# Dout24x.net
KiCad netlist of a schematic drawn in Altium Designer
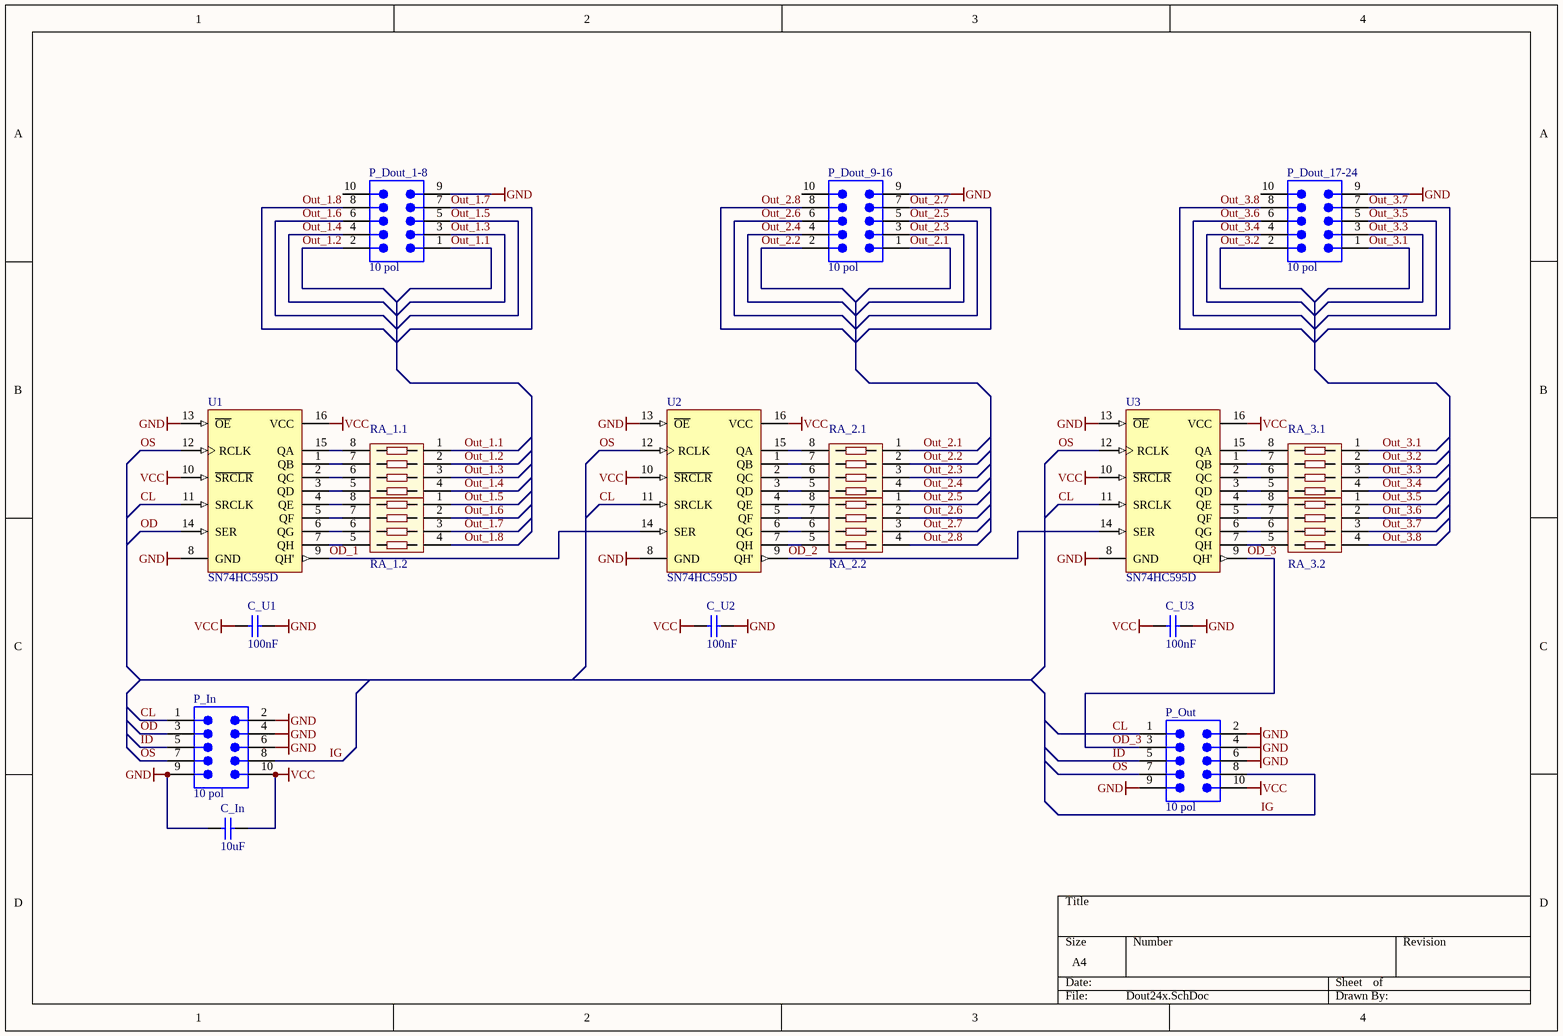
[diagram p0: Dout24x.SchDoc]

(export (version "E")
  (design (tool "Eeschema 10.0.6"))
  (components
    (comp (ref "C_In")
      (value "10uF")
      (footprint "1608[0603]")
      (description "Capacitor (Semiconductor SIM Model)")
      (fields (field (name "Comment") "Cap Semi") (field (name "PUBLISHER") "Altium Limited"))
      (libsource (lib "Miscellaneous Devices") (part "Cap Semi"))
    )
    (comp (ref "C_U1")
      (value "100nF")
      (footprint "1608[0603]")
      (description "Capacitor (Semiconductor SIM Model)")
      (fields (field (name "Comment") "Cap Semi") (field (name "PUBLISHER") "Altium Limited"))
      (libsource (lib "Miscellaneous Devices") (part "Cap Semi"))
    )
    (comp (ref "C_U2")
      (value "100nF")
      (footprint "1608[0603]")
      (description "Capacitor (Semiconductor SIM Model)")
      (fields (field (name "Comment") "Cap Semi") (field (name "PUBLISHER") "Altium Limited"))
      (libsource (lib "Miscellaneous Devices") (part "Cap Semi"))
    )
    (comp (ref "C_U3")
      (value "100nF")
      (footprint "1608[0603]")
      (description "Capacitor (Semiconductor SIM Model)")
      (fields (field (name "Comment") "Cap Semi") (field (name "PUBLISHER") "Altium Limited"))
      (libsource (lib "Miscellaneous Devices") (part "Cap Semi"))
    )
    (comp (ref "P_Dout_1-8")
      (value "10 pol")
      (footprint "918510x324")
      (fields (field (name "PUBLISHER") "Altium Limited"))
      (libsource (lib "HARTING IDC 2.54mm Pitch") (part "09 18 510 6324"))
    )
    (comp (ref "P_Dout_9-16")
      (value "10 pol")
      (footprint "918510x324")
      (fields (field (name "PUBLISHER") "Altium Limited"))
      (libsource (lib "HARTING IDC 2.54mm Pitch") (part "09 18 510 6324"))
    )
    (comp (ref "P_Dout_17-24")
      (value "10 pol")
      (footprint "918510x324")
      (fields (field (name "PUBLISHER") "Altium Limited"))
      (libsource (lib "HARTING IDC 2.54mm Pitch") (part "09 18 510 6324"))
    )
    (comp (ref "P_In")
      (value "10 pol")
      (footprint "918510x324")
      (fields (field (name "PUBLISHER") "Altium Limited"))
      (libsource (lib "") (part "09 18 510 6324_1"))
    )
    (comp (ref "P_Out")
      (value "10 pol")
      (footprint "918510x324")
      (fields (field (name "PUBLISHER") "Altium Limited"))
      (libsource (lib "") (part "09 18 510 6324_1"))
    )
    (comp (ref "RA_1.1")
      (value "EXB38")
      (footprint "Panasonic EXB38V:EXB38")
      (fields (field (name "PUBLISHER") "Altium Limited"))
      (libsource (lib "Panasonic Resistor Array") (part "4 Resistors Parallel"))
    )
    (comp (ref "RA_1.2")
      (value "EXB38")
      (footprint "Panasonic EXB38V:EXB38")
      (fields (field (name "PUBLISHER") "Altium Limited"))
      (libsource (lib "Panasonic Resistor Array") (part "4 Resistors Parallel"))
    )
    (comp (ref "RA_2.1")
      (value "EXB38")
      (footprint "Panasonic EXB38V:EXB38")
      (fields (field (name "PUBLISHER") "Altium Limited"))
      (libsource (lib "Panasonic Resistor Array") (part "4 Resistors Parallel"))
    )
    (comp (ref "RA_2.2")
      (value "EXB38")
      (footprint "Panasonic EXB38V:EXB38")
      (fields (field (name "PUBLISHER") "Altium Limited"))
      (libsource (lib "Panasonic Resistor Array") (part "4 Resistors Parallel"))
    )
    (comp (ref "RA_3.1")
      (value "EXB38")
      (footprint "Panasonic EXB38V:EXB38")
      (fields (field (name "PUBLISHER") "Altium Limited"))
      (libsource (lib "Panasonic Resistor Array") (part "4 Resistors Parallel"))
    )
    (comp (ref "RA_3.2")
      (value "EXB38")
      (footprint "Panasonic EXB38V:EXB38")
      (fields (field (name "PUBLISHER") "Altium Limited"))
      (libsource (lib "Panasonic Resistor Array") (part "4 Resistors Parallel"))
    )
    (comp (ref "U1")
      (value "SN74HC595D")
      (footprint "D016_N")
      (description "8-Bit Shift Register with 3-State Output Registers")
      (fields (field (name "PUBLISHER") "Altium Limited"))
      (libsource (lib "TI Logic Register") (part "SN74HC595D"))
    )
    (comp (ref "U2")
      (value "SN74HC595D")
      (footprint "D016_N")
      (description "8-Bit Shift Register with 3-State Output Registers")
      (fields (field (name "PUBLISHER") "Altium Limited"))
      (libsource (lib "TI Logic Register") (part "SN74HC595D"))
    )
    (comp (ref "U3")
      (value "SN74HC595D")
      (footprint "D016_N")
      (description "8-Bit Shift Register with 3-State Output Registers")
      (fields (field (name "PUBLISHER") "Altium Limited"))
      (libsource (lib "TI Logic Register") (part "SN74HC595D"))
    )
  )
  (nets
    (net (code "1") (name "/CL") (class "Default")
      (node (ref "P_In") (pin "1") (pinfunction "1_1") (pintype "passive"))
      (node (ref "P_Out") (pin "1") (pinfunction "1_1") (pintype "passive"))
      (node (ref "U1") (pin "11") (pinfunction "SRCLK_11") (pintype "input"))
      (node (ref "U2") (pin "11") (pinfunction "SRCLK_11") (pintype "input"))
      (node (ref "U3") (pin "11") (pinfunction "SRCLK_11") (pintype "input"))
    )
    (net (code "2") (name "/ID") (class "Default")
      (node (ref "P_In") (pin "5") (pinfunction "5_5") (pintype "passive"))
      (node (ref "P_Out") (pin "5") (pinfunction "5_5") (pintype "passive"))
    )
    (net (code "3") (name "/IG") (class "Default")
      (node (ref "P_In") (pin "8") (pinfunction "8_8") (pintype "passive"))
      (node (ref "P_Out") (pin "8") (pinfunction "8_8") (pintype "passive"))
    )
    (net (code "4") (name "/OD") (class "Default")
      (node (ref "P_In") (pin "3") (pinfunction "3_3") (pintype "passive"))
      (node (ref "U1") (pin "14") (pinfunction "SER_14") (pintype "input"))
    )
    (net (code "5") (name "/OD_1") (class "Default")
      (node (ref "U1") (pin "9") (pinfunction "QH'_9") (pintype "output"))
      (node (ref "U2") (pin "14") (pinfunction "SER_14") (pintype "input"))
    )
    (net (code "6") (name "/OD_2") (class "Default")
      (node (ref "U2") (pin "9") (pinfunction "QH'_9") (pintype "output"))
      (node (ref "U3") (pin "14") (pinfunction "SER_14") (pintype "input"))
    )
    (net (code "7") (name "/OD_3") (class "Default")
      (node (ref "P_Out") (pin "3") (pinfunction "3_3") (pintype "passive"))
      (node (ref "U3") (pin "9") (pinfunction "QH'_9") (pintype "output"))
    )
    (net (code "8") (name "/OS") (class "Default")
      (node (ref "P_In") (pin "7") (pinfunction "7_7") (pintype "passive"))
      (node (ref "P_Out") (pin "7") (pinfunction "7_7") (pintype "passive"))
      (node (ref "U1") (pin "12") (pinfunction "RCLK_12") (pintype "input"))
      (node (ref "U2") (pin "12") (pinfunction "RCLK_12") (pintype "input"))
      (node (ref "U3") (pin "12") (pinfunction "RCLK_12") (pintype "input"))
    )
    (net (code "9") (name "/Out_1.1") (class "Default")
      (node (ref "P_Dout_1-8") (pin "1") (pinfunction "1_1") (pintype "passive"))
      (node (ref "RA_1.1") (pin "1") (pinfunction "1_1") (pintype "passive"))
    )
    (net (code "10") (name "/Out_1.2") (class "Default")
      (node (ref "P_Dout_1-8") (pin "2") (pinfunction "2_2") (pintype "passive"))
      (node (ref "RA_1.1") (pin "2") (pinfunction "2_2") (pintype "passive"))
    )
    (net (code "11") (name "/Out_1.3") (class "Default")
      (node (ref "P_Dout_1-8") (pin "3") (pinfunction "3_3") (pintype "passive"))
      (node (ref "RA_1.1") (pin "3") (pinfunction "3_3") (pintype "passive"))
    )
    (net (code "12") (name "/Out_1.4") (class "Default")
      (node (ref "P_Dout_1-8") (pin "4") (pinfunction "4_4") (pintype "passive"))
      (node (ref "RA_1.1") (pin "4") (pinfunction "4_4") (pintype "passive"))
    )
    (net (code "13") (name "/Out_1.5") (class "Default")
      (node (ref "P_Dout_1-8") (pin "5") (pinfunction "5_5") (pintype "passive"))
      (node (ref "RA_1.2") (pin "1") (pinfunction "1_1") (pintype "passive"))
    )
    (net (code "14") (name "/Out_1.6") (class "Default")
      (node (ref "P_Dout_1-8") (pin "6") (pinfunction "6_6") (pintype "passive"))
      (node (ref "RA_1.2") (pin "2") (pinfunction "2_2") (pintype "passive"))
    )
    (net (code "15") (name "/Out_1.7") (class "Default")
      (node (ref "P_Dout_1-8") (pin "7") (pinfunction "7_7") (pintype "passive"))
      (node (ref "RA_1.2") (pin "3") (pinfunction "3_3") (pintype "passive"))
    )
    (net (code "16") (name "/Out_1.8") (class "Default")
      (node (ref "P_Dout_1-8") (pin "8") (pinfunction "8_8") (pintype "passive"))
      (node (ref "RA_1.2") (pin "4") (pinfunction "4_4") (pintype "passive"))
    )
    (net (code "17") (name "/Out_2.1") (class "Default")
      (node (ref "P_Dout_9-16") (pin "1") (pinfunction "1_1") (pintype "passive"))
      (node (ref "RA_2.1") (pin "1") (pinfunction "1_1") (pintype "passive"))
    )
    (net (code "18") (name "/Out_2.2") (class "Default")
      (node (ref "P_Dout_9-16") (pin "2") (pinfunction "2_2") (pintype "passive"))
      (node (ref "RA_2.1") (pin "2") (pinfunction "2_2") (pintype "passive"))
    )
    (net (code "19") (name "/Out_2.3") (class "Default")
      (node (ref "P_Dout_9-16") (pin "3") (pinfunction "3_3") (pintype "passive"))
      (node (ref "RA_2.1") (pin "3") (pinfunction "3_3") (pintype "passive"))
    )
    (net (code "20") (name "/Out_2.4") (class "Default")
      (node (ref "P_Dout_9-16") (pin "4") (pinfunction "4_4") (pintype "passive"))
      (node (ref "RA_2.1") (pin "4") (pinfunction "4_4") (pintype "passive"))
    )
    (net (code "21") (name "/Out_2.5") (class "Default")
      (node (ref "P_Dout_9-16") (pin "5") (pinfunction "5_5") (pintype "passive"))
      (node (ref "RA_2.2") (pin "1") (pinfunction "1_1") (pintype "passive"))
    )
    (net (code "22") (name "/Out_2.6") (class "Default")
      (node (ref "P_Dout_9-16") (pin "6") (pinfunction "6_6") (pintype "passive"))
      (node (ref "RA_2.2") (pin "2") (pinfunction "2_2") (pintype "passive"))
    )
    (net (code "23") (name "/Out_2.7") (class "Default")
      (node (ref "P_Dout_9-16") (pin "7") (pinfunction "7_7") (pintype "passive"))
      (node (ref "RA_2.2") (pin "3") (pinfunction "3_3") (pintype "passive"))
    )
    (net (code "24") (name "/Out_2.8") (class "Default")
      (node (ref "P_Dout_9-16") (pin "8") (pinfunction "8_8") (pintype "passive"))
      (node (ref "RA_2.2") (pin "4") (pinfunction "4_4") (pintype "passive"))
    )
    (net (code "25") (name "/Out_3.1") (class "Default")
      (node (ref "P_Dout_17-24") (pin "1") (pinfunction "1_1") (pintype "passive"))
      (node (ref "RA_3.1") (pin "1") (pinfunction "1_1") (pintype "passive"))
    )
    (net (code "26") (name "/Out_3.2") (class "Default")
      (node (ref "P_Dout_17-24") (pin "2") (pinfunction "2_2") (pintype "passive"))
      (node (ref "RA_3.1") (pin "2") (pinfunction "2_2") (pintype "passive"))
    )
    (net (code "27") (name "/Out_3.3") (class "Default")
      (node (ref "P_Dout_17-24") (pin "3") (pinfunction "3_3") (pintype "passive"))
      (node (ref "RA_3.1") (pin "3") (pinfunction "3_3") (pintype "passive"))
    )
    (net (code "28") (name "/Out_3.4") (class "Default")
      (node (ref "P_Dout_17-24") (pin "4") (pinfunction "4_4") (pintype "passive"))
      (node (ref "RA_3.1") (pin "4") (pinfunction "4_4") (pintype "passive"))
    )
    (net (code "29") (name "/Out_3.5") (class "Default")
      (node (ref "P_Dout_17-24") (pin "5") (pinfunction "5_5") (pintype "passive"))
      (node (ref "RA_3.2") (pin "1") (pinfunction "1_1") (pintype "passive"))
    )
    (net (code "30") (name "/Out_3.6") (class "Default")
      (node (ref "P_Dout_17-24") (pin "6") (pinfunction "6_6") (pintype "passive"))
      (node (ref "RA_3.2") (pin "2") (pinfunction "2_2") (pintype "passive"))
    )
    (net (code "31") (name "/Out_3.7") (class "Default")
      (node (ref "P_Dout_17-24") (pin "7") (pinfunction "7_7") (pintype "passive"))
      (node (ref "RA_3.2") (pin "3") (pinfunction "3_3") (pintype "passive"))
    )
    (net (code "32") (name "/Out_3.8") (class "Default")
      (node (ref "P_Dout_17-24") (pin "8") (pinfunction "8_8") (pintype "passive"))
      (node (ref "RA_3.2") (pin "4") (pinfunction "4_4") (pintype "passive"))
    )
    (net (code "33") (name "GND") (class "Default")
      (node (ref "C_In") (pin "1") (pinfunction "1_1") (pintype "passive"))
      (node (ref "C_U1") (pin "1") (pinfunction "1_1") (pintype "passive"))
      (node (ref "C_U2") (pin "1") (pinfunction "1_1") (pintype "passive"))
      (node (ref "C_U3") (pin "1") (pinfunction "1_1") (pintype "passive"))
      (node (ref "P_Dout_1-8") (pin "9") (pinfunction "9_9") (pintype "passive"))
      (node (ref "P_Dout_17-24") (pin "9") (pinfunction "9_9") (pintype "passive"))
      (node (ref "P_Dout_9-16") (pin "9") (pinfunction "9_9") (pintype "passive"))
      (node (ref "P_In") (pin "2") (pinfunction "2_2") (pintype "passive"))
      (node (ref "P_In") (pin "4") (pinfunction "4_4") (pintype "passive"))
      (node (ref "P_In") (pin "6") (pinfunction "6_6") (pintype "passive"))
      (node (ref "P_In") (pin "9") (pinfunction "9_9") (pintype "passive"))
      (node (ref "P_Out") (pin "2") (pinfunction "2_2") (pintype "passive"))
      (node (ref "P_Out") (pin "4") (pinfunction "4_4") (pintype "passive"))
      (node (ref "P_Out") (pin "6") (pinfunction "6_6") (pintype "passive"))
      (node (ref "P_Out") (pin "9") (pinfunction "9_9") (pintype "passive"))
      (node (ref "U1") (pin "13") (pinfunction "~{OE}_13") (pintype "input"))
      (node (ref "U1") (pin "8") (pinfunction "GND_8") (pintype "power_in"))
      (node (ref "U2") (pin "13") (pinfunction "~{OE}_13") (pintype "input"))
      (node (ref "U2") (pin "8") (pinfunction "GND_8") (pintype "power_in"))
      (node (ref "U3") (pin "13") (pinfunction "~{OE}_13") (pintype "input"))
      (node (ref "U3") (pin "8") (pinfunction "GND_8") (pintype "power_in"))
    )
    (net (code "34") (name "Net-(U1-QA)") (class "Default")
      (node (ref "RA_1.1") (pin "8") (pinfunction "8_8") (pintype "passive"))
      (node (ref "U1") (pin "15") (pinfunction "QA_15") (pintype "tri_state"))
    )
    (net (code "35") (name "Net-(U1-QB)") (class "Default")
      (node (ref "RA_1.1") (pin "7") (pinfunction "7_7") (pintype "passive"))
      (node (ref "U1") (pin "1") (pinfunction "QB_1") (pintype "tri_state"))
    )
    (net (code "36") (name "Net-(U1-QC)") (class "Default")
      (node (ref "RA_1.1") (pin "6") (pinfunction "6_6") (pintype "passive"))
      (node (ref "U1") (pin "2") (pinfunction "QC_2") (pintype "tri_state"))
    )
    (net (code "37") (name "Net-(U1-QD)") (class "Default")
      (node (ref "RA_1.1") (pin "5") (pinfunction "5_5") (pintype "passive"))
      (node (ref "U1") (pin "3") (pinfunction "QD_3") (pintype "tri_state"))
    )
    (net (code "38") (name "Net-(U1-QE)") (class "Default")
      (node (ref "RA_1.2") (pin "8") (pinfunction "8_8") (pintype "passive"))
      (node (ref "U1") (pin "4") (pinfunction "QE_4") (pintype "tri_state"))
    )
    (net (code "39") (name "Net-(U1-QF)") (class "Default")
      (node (ref "RA_1.2") (pin "7") (pinfunction "7_7") (pintype "passive"))
      (node (ref "U1") (pin "5") (pinfunction "QF_5") (pintype "tri_state"))
    )
    (net (code "40") (name "Net-(U1-QG)") (class "Default")
      (node (ref "RA_1.2") (pin "6") (pinfunction "6_6") (pintype "passive"))
      (node (ref "U1") (pin "6") (pinfunction "QG_6") (pintype "tri_state"))
    )
    (net (code "41") (name "Net-(U1-QH)") (class "Default")
      (node (ref "RA_1.2") (pin "5") (pinfunction "5_5") (pintype "passive"))
      (node (ref "U1") (pin "7") (pinfunction "QH_7") (pintype "tri_state"))
    )
    (net (code "42") (name "Net-(U2-QA)") (class "Default")
      (node (ref "RA_2.1") (pin "8") (pinfunction "8_8") (pintype "passive"))
      (node (ref "U2") (pin "15") (pinfunction "QA_15") (pintype "tri_state"))
    )
    (net (code "43") (name "Net-(U2-QB)") (class "Default")
      (node (ref "RA_2.1") (pin "7") (pinfunction "7_7") (pintype "passive"))
      (node (ref "U2") (pin "1") (pinfunction "QB_1") (pintype "tri_state"))
    )
    (net (code "44") (name "Net-(U2-QC)") (class "Default")
      (node (ref "RA_2.1") (pin "6") (pinfunction "6_6") (pintype "passive"))
      (node (ref "U2") (pin "2") (pinfunction "QC_2") (pintype "tri_state"))
    )
    (net (code "45") (name "Net-(U2-QD)") (class "Default")
      (node (ref "RA_2.1") (pin "5") (pinfunction "5_5") (pintype "passive"))
      (node (ref "U2") (pin "3") (pinfunction "QD_3") (pintype "tri_state"))
    )
    (net (code "46") (name "Net-(U2-QE)") (class "Default")
      (node (ref "RA_2.2") (pin "8") (pinfunction "8_8") (pintype "passive"))
      (node (ref "U2") (pin "4") (pinfunction "QE_4") (pintype "tri_state"))
    )
    (net (code "47") (name "Net-(U2-QF)") (class "Default")
      (node (ref "RA_2.2") (pin "7") (pinfunction "7_7") (pintype "passive"))
      (node (ref "U2") (pin "5") (pinfunction "QF_5") (pintype "tri_state"))
    )
    (net (code "48") (name "Net-(U2-QG)") (class "Default")
      (node (ref "RA_2.2") (pin "6") (pinfunction "6_6") (pintype "passive"))
      (node (ref "U2") (pin "6") (pinfunction "QG_6") (pintype "tri_state"))
    )
    (net (code "49") (name "Net-(U2-QH)") (class "Default")
      (node (ref "RA_2.2") (pin "5") (pinfunction "5_5") (pintype "passive"))
      (node (ref "U2") (pin "7") (pinfunction "QH_7") (pintype "tri_state"))
    )
    (net (code "50") (name "Net-(U3-QA)") (class "Default")
      (node (ref "RA_3.1") (pin "8") (pinfunction "8_8") (pintype "passive"))
      (node (ref "U3") (pin "15") (pinfunction "QA_15") (pintype "tri_state"))
    )
    (net (code "51") (name "Net-(U3-QB)") (class "Default")
      (node (ref "RA_3.1") (pin "7") (pinfunction "7_7") (pintype "passive"))
      (node (ref "U3") (pin "1") (pinfunction "QB_1") (pintype "tri_state"))
    )
    (net (code "52") (name "Net-(U3-QC)") (class "Default")
      (node (ref "RA_3.1") (pin "6") (pinfunction "6_6") (pintype "passive"))
      (node (ref "U3") (pin "2") (pinfunction "QC_2") (pintype "tri_state"))
    )
    (net (code "53") (name "Net-(U3-QD)") (class "Default")
      (node (ref "RA_3.1") (pin "5") (pinfunction "5_5") (pintype "passive"))
      (node (ref "U3") (pin "3") (pinfunction "QD_3") (pintype "tri_state"))
    )
    (net (code "54") (name "Net-(U3-QE)") (class "Default")
      (node (ref "RA_3.2") (pin "8") (pinfunction "8_8") (pintype "passive"))
      (node (ref "U3") (pin "4") (pinfunction "QE_4") (pintype "tri_state"))
    )
    (net (code "55") (name "Net-(U3-QF)") (class "Default")
      (node (ref "RA_3.2") (pin "7") (pinfunction "7_7") (pintype "passive"))
      (node (ref "U3") (pin "5") (pinfunction "QF_5") (pintype "tri_state"))
    )
    (net (code "56") (name "Net-(U3-QG)") (class "Default")
      (node (ref "RA_3.2") (pin "6") (pinfunction "6_6") (pintype "passive"))
      (node (ref "U3") (pin "6") (pinfunction "QG_6") (pintype "tri_state"))
    )
    (net (code "57") (name "Net-(U3-QH)") (class "Default")
      (node (ref "RA_3.2") (pin "5") (pinfunction "5_5") (pintype "passive"))
      (node (ref "U3") (pin "7") (pinfunction "QH_7") (pintype "tri_state"))
    )
    (net (code "58") (name "VCC") (class "Default")
      (node (ref "C_In") (pin "2") (pinfunction "2_2") (pintype "passive"))
      (node (ref "C_U1") (pin "2") (pinfunction "2_2") (pintype "passive"))
      (node (ref "C_U2") (pin "2") (pinfunction "2_2") (pintype "passive"))
      (node (ref "C_U3") (pin "2") (pinfunction "2_2") (pintype "passive"))
      (node (ref "P_In") (pin "10") (pinfunction "10_10") (pintype "passive"))
      (node (ref "P_Out") (pin "10") (pinfunction "10_10") (pintype "passive"))
      (node (ref "U1") (pin "10") (pinfunction "~{SRCLR}_10") (pintype "input"))
      (node (ref "U1") (pin "16") (pinfunction "VCC_16") (pintype "power_in"))
      (node (ref "U2") (pin "10") (pinfunction "~{SRCLR}_10") (pintype "input"))
      (node (ref "U2") (pin "16") (pinfunction "VCC_16") (pintype "power_in"))
      (node (ref "U3") (pin "10") (pinfunction "~{SRCLR}_10") (pintype "input"))
      (node (ref "U3") (pin "16") (pinfunction "VCC_16") (pintype "power_in"))
    )
    (net (code "59") (name "unconnected-(P_Dout_1-8-Pad10)") (class "Default")
      (node (ref "P_Dout_1-8") (pin "10") (pinfunction "10_10") (pintype "passive"))
    )
    (net (code "60") (name "unconnected-(P_Dout_9-16-Pad10)") (class "Default")
      (node (ref "P_Dout_9-16") (pin "10") (pinfunction "10_10") (pintype "passive"))
    )
    (net (code "61") (name "unconnected-(P_Dout_17-24-Pad10)") (class "Default")
      (node (ref "P_Dout_17-24") (pin "10") (pinfunction "10_10") (pintype "passive"))
    )
  )
)
